# Microcontroller.net
KiCad netlist of a schematic drawn in Altium Designer
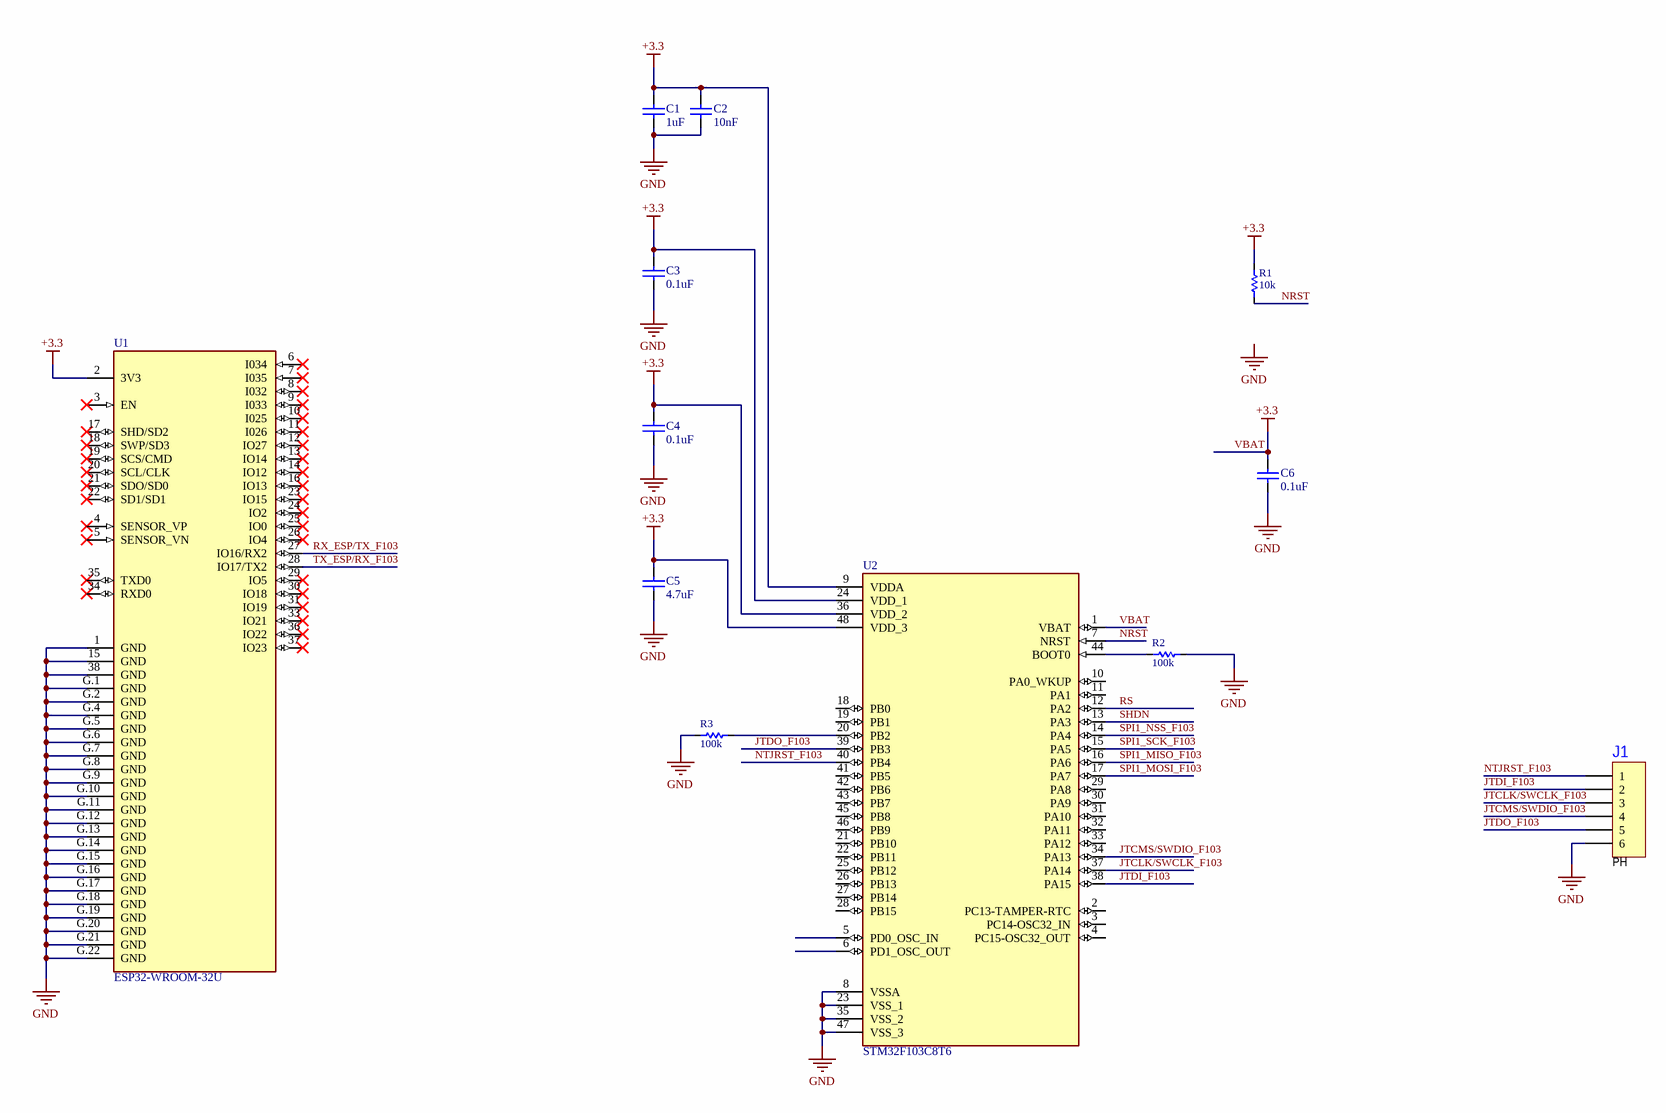
[diagram p0: Microcontroller.SchDoc]

(export (version "E")
  (design (tool "Eeschema 10.0.6"))
  (components
    (comp (ref "C1")
      (value "1uF")
      (footprint "CAPC2012X135N")
      (description "Capacitor SMD Ceramic Chip Cap 0.1uF 50V (0805) (AVX)")
      (fields (field (name "CREATED BY") "Zion Blue") (field (name "PUBLISHER") "Cynetik Group"))
      (libsource (lib "StylishSchematic") (part "CAP_0.1_50V_0805"))
    )
    (comp (ref "C2")
      (value "10nF")
      (footprint "CAPC2012X135N")
      (description "Capacitor SMD Ceramic Chip Cap 0.1uF 50V (0805) (AVX)")
      (fields (field (name "CREATED BY") "Zion Blue") (field (name "PUBLISHER") "Cynetik Group"))
      (libsource (lib "StylishSchematic") (part "CAP_0.1_50V_0805"))
    )
    (comp (ref "C3")
      (value "0.1uF")
      (footprint "CAPC2012X135N")
      (description "Capacitor SMD Ceramic Chip Cap 0.1uF 50V (0805) (AVX)")
      (fields (field (name "CREATED BY") "Zion Blue") (field (name "PUBLISHER") "Cynetik Group"))
      (libsource (lib "StylishSchematic") (part "CAP_0.1_50V_0805"))
    )
    (comp (ref "C4")
      (value "0.1uF")
      (footprint "CAPC2012X135N")
      (description "Capacitor SMD Ceramic Chip Cap 0.1uF 50V (0805) (AVX)")
      (fields (field (name "CREATED BY") "Zion Blue") (field (name "PUBLISHER") "Cynetik Group"))
      (libsource (lib "StylishSchematic") (part "CAP_0.1_50V_0805"))
    )
    (comp (ref "C5")
      (value "4.7uF")
      (footprint "CAPC2012X135N")
      (description "Capacitor SMD Ceramic Chip Cap 0.1uF 50V (0805) (AVX)")
      (fields (field (name "CREATED BY") "Zion Blue") (field (name "PUBLISHER") "Cynetik Group"))
      (libsource (lib "StylishSchematic") (part "CAP_0.1_50V_0805"))
    )
    (comp (ref "C6")
      (value "0.1uF")
      (footprint "CAPC2012X135N")
      (description "Capacitor SMD Ceramic Chip Cap 0.1uF 50V (0805) (AVX)")
      (fields (field (name "CREATED BY") "Zion Blue") (field (name "PUBLISHER") "Cynetik Group"))
      (libsource (lib "StylishSchematic") (part "CAP_0.1_50V_0805"))
    )
    (comp (ref "J1")
      (value "PH")
      (footprint "HDR1X6")
      (description "Connector 6 x 1 PIN Header 2.54 x 2.54 mm")
      (fields (field (name "PUBLISHER") "Altium Limited"))
      (libsource (lib "StylishSchematic") (part "Connector 6x1 Pin Header"))
    )
    (comp (ref "R1")
      (value "10k")
      (footprint "0805 MODIFICADO")
      (description "0805 100K OHM Resistor .")
      (libsource (lib "StylishSchematic") (part "RES_100K_1/8W_0805"))
    )
    (comp (ref "R2")
      (value "100k")
      (footprint "0805 MODIFICADO")
      (description "0805 100K OHM Resistor .")
      (libsource (lib "StylishSchematic") (part "RES_100K_1/8W_0805"))
    )
    (comp (ref "R3")
      (value "100k")
      (footprint "0805 MODIFICADO")
      (description "0805 100K OHM Resistor .")
      (libsource (lib "StylishSchematic") (part "RES_100K_1/8W_0805"))
    )
    (comp (ref "U1")
      (value "ESP32-WROOM-32U")
      (footprint "XCVR_ESP32-WROOM-32U")
      (fields (field (name "MF") "Espressif Systems"))
      (libsource (lib "StylishSchematic") (part "ESP32-WROOM-32U"))
    )
    (comp (ref "U2")
      (value "STM32F103C8T6")
      (footprint "QFP50P900X900X160-48N")
      (description "ARM® Cortex®-M3 STM32F1 Microcontroller IC 32-Bit 72MHz 64KB (64K x 8) FLASH 48-LQFP (7x7)")
      (fields (field (name "MF") "STMicroelectronics"))
      (libsource (lib "StylishSchematic") (part "STM32F103C8T6"))
    )
  )
  (nets
    (net (code "1") (name "+3.3") (class "Default")
      (node (ref "C1") (pin "2") (pinfunction "2_2") (pintype "passive"))
      (node (ref "C2") (pin "2") (pinfunction "2_2") (pintype "passive"))
      (node (ref "C3") (pin "2") (pinfunction "2_2") (pintype "passive"))
      (node (ref "C4") (pin "2") (pinfunction "2_2") (pintype "passive"))
      (node (ref "C5") (pin "2") (pinfunction "2_2") (pintype "passive"))
      (node (ref "C6") (pin "2") (pinfunction "2_2") (pintype "passive"))
      (node (ref "R1") (pin "2") (pinfunction "2_2") (pintype "passive"))
      (node (ref "U1") (pin "2") (pinfunction "3V3_2") (pintype "power_in"))
      (node (ref "U2") (pin "1") (pinfunction "VBAT_1") (pintype "bidirectional"))
      (node (ref "U2") (pin "24") (pinfunction "VDD_1_24") (pintype "power_in"))
      (node (ref "U2") (pin "36") (pinfunction "VDD_2_36") (pintype "power_in"))
      (node (ref "U2") (pin "48") (pinfunction "VDD_3_48") (pintype "power_in"))
      (node (ref "U2") (pin "9") (pinfunction "VDDA_9") (pintype "power_in"))
    )
    (net (code "2") (name "/JTCLK{slash}SWCLK_F103") (class "Default")
      (node (ref "J1") (pin "3") (pinfunction "3_3") (pintype "passive"))
      (node (ref "U2") (pin "37") (pinfunction "PA14_37") (pintype "bidirectional"))
    )
    (net (code "3") (name "/JTCMS{slash}SWDIO_F103") (class "Default")
      (node (ref "J1") (pin "4") (pinfunction "4_4") (pintype "passive"))
      (node (ref "U2") (pin "34") (pinfunction "PA13_34") (pintype "bidirectional"))
    )
    (net (code "4") (name "/JTDI_F103") (class "Default")
      (node (ref "J1") (pin "2") (pinfunction "2_2") (pintype "passive"))
      (node (ref "U2") (pin "38") (pinfunction "PA15_38") (pintype "bidirectional"))
    )
    (net (code "5") (name "/JTDO_F103") (class "Default")
      (node (ref "J1") (pin "5") (pinfunction "5_5") (pintype "passive"))
      (node (ref "U2") (pin "39") (pinfunction "PB3_39") (pintype "bidirectional"))
    )
    (net (code "6") (name "/NRST") (class "Default")
      (node (ref "R1") (pin "1") (pinfunction "1_1") (pintype "passive"))
      (node (ref "U2") (pin "7") (pinfunction "NRST_7") (pintype "input"))
    )
    (net (code "7") (name "/NTJRST_F103") (class "Default")
      (node (ref "J1") (pin "1") (pinfunction "1_1") (pintype "passive"))
      (node (ref "U2") (pin "40") (pinfunction "PB4_40") (pintype "bidirectional"))
    )
    (net (code "8") (name "/RS") (class "Default")
      (node (ref "U2") (pin "12") (pinfunction "PA2_12") (pintype "bidirectional"))
    )
    (net (code "9") (name "/RX_ESP{slash}TX_F103") (class "Default")
      (node (ref "U1") (pin "27") (pinfunction "IO16/RX2_27") (pintype "bidirectional"))
    )
    (net (code "10") (name "/SHDN") (class "Default")
      (node (ref "U2") (pin "13") (pinfunction "PA3_13") (pintype "bidirectional"))
    )
    (net (code "11") (name "/SPI1_MISO_F103") (class "Default")
      (node (ref "U2") (pin "16") (pinfunction "PA6_16") (pintype "bidirectional"))
    )
    (net (code "12") (name "/SPI1_MOSI_F103") (class "Default")
      (node (ref "U2") (pin "17") (pinfunction "PA7_17") (pintype "bidirectional"))
    )
    (net (code "13") (name "/SPI1_NSS_F103") (class "Default")
      (node (ref "U2") (pin "14") (pinfunction "PA4_14") (pintype "bidirectional"))
    )
    (net (code "14") (name "/SPI1_SCK_F103") (class "Default")
      (node (ref "U2") (pin "15") (pinfunction "PA5_15") (pintype "bidirectional"))
    )
    (net (code "15") (name "/TX_ESP{slash}RX_F103") (class "Default")
      (node (ref "U1") (pin "28") (pinfunction "IO17/TX2_28") (pintype "bidirectional"))
    )
    (net (code "16") (name "GND") (class "Default")
      (node (ref "C1") (pin "1") (pinfunction "1_1") (pintype "passive"))
      (node (ref "C2") (pin "1") (pinfunction "1_1") (pintype "passive"))
      (node (ref "C3") (pin "1") (pinfunction "1_1") (pintype "passive"))
      (node (ref "C4") (pin "1") (pinfunction "1_1") (pintype "passive"))
      (node (ref "C5") (pin "1") (pinfunction "1_1") (pintype "passive"))
      (node (ref "C6") (pin "1") (pinfunction "1_1") (pintype "passive"))
      (node (ref "J1") (pin "6") (pinfunction "6_6") (pintype "passive"))
      (node (ref "R2") (pin "2") (pinfunction "2_2") (pintype "passive"))
      (node (ref "R3") (pin "1") (pinfunction "1_1") (pintype "passive"))
      (node (ref "U1") (pin "1") (pinfunction "GND_1") (pintype "power_in"))
      (node (ref "U1") (pin "15") (pinfunction "GND_15") (pintype "power_in"))
      (node (ref "U1") (pin "38") (pinfunction "GND_38") (pintype "power_in"))
      (node (ref "U1") (pin "G.1") (pinfunction "GND_G.1") (pintype "power_in"))
      (node (ref "U1") (pin "G.10") (pinfunction "GND_G.10") (pintype "power_in"))
      (node (ref "U1") (pin "G.11") (pinfunction "GND_G.11") (pintype "power_in"))
      (node (ref "U1") (pin "G.12") (pinfunction "GND_G.12") (pintype "power_in"))
      (node (ref "U1") (pin "G.13") (pinfunction "GND_G.13") (pintype "power_in"))
      (node (ref "U1") (pin "G.14") (pinfunction "GND_G.14") (pintype "power_in"))
      (node (ref "U1") (pin "G.15") (pinfunction "GND_G.15") (pintype "power_in"))
      (node (ref "U1") (pin "G.16") (pinfunction "GND_G.16") (pintype "power_in"))
      (node (ref "U1") (pin "G.17") (pinfunction "GND_G.17") (pintype "power_in"))
      (node (ref "U1") (pin "G.18") (pinfunction "GND_G.18") (pintype "power_in"))
      (node (ref "U1") (pin "G.19") (pinfunction "GND_G.19") (pintype "power_in"))
      (node (ref "U1") (pin "G.2") (pinfunction "GND_G.2") (pintype "power_in"))
      (node (ref "U1") (pin "G.20") (pinfunction "GND_G.20") (pintype "power_in"))
      (node (ref "U1") (pin "G.21") (pinfunction "GND_G.21") (pintype "power_in"))
      (node (ref "U1") (pin "G.22") (pinfunction "GND_G.22") (pintype "power_in"))
      (node (ref "U1") (pin "G.4") (pinfunction "GND_G.4") (pintype "power_in"))
      (node (ref "U1") (pin "G.5") (pinfunction "GND_G.5") (pintype "power_in"))
      (node (ref "U1") (pin "G.6") (pinfunction "GND_G.6") (pintype "power_in"))
      (node (ref "U1") (pin "G.7") (pinfunction "GND_G.7") (pintype "power_in"))
      (node (ref "U1") (pin "G.8") (pinfunction "GND_G.8") (pintype "power_in"))
      (node (ref "U1") (pin "G.9") (pinfunction "GND_G.9") (pintype "power_in"))
      (node (ref "U2") (pin "23") (pinfunction "VSS_1_23") (pintype "power_in"))
      (node (ref "U2") (pin "35") (pinfunction "VSS_2_35") (pintype "power_in"))
      (node (ref "U2") (pin "47") (pinfunction "VSS_3_47") (pintype "power_in"))
      (node (ref "U2") (pin "8") (pinfunction "VSSA_8") (pintype "power_in"))
    )
    (net (code "17") (name "Net-(U2-BOOT0)") (class "Default")
      (node (ref "R2") (pin "1") (pinfunction "1_1") (pintype "passive"))
      (node (ref "U2") (pin "44") (pinfunction "BOOT0_44") (pintype "input"))
    )
    (net (code "18") (name "Net-(U2-PB2)") (class "Default")
      (node (ref "R3") (pin "2") (pinfunction "2_2") (pintype "passive"))
      (node (ref "U2") (pin "20") (pinfunction "PB2_20") (pintype "bidirectional"))
    )
    (net (code "19") (name "unconnected-(U1-EN-Pad3)") (class "Default")
      (node (ref "U1") (pin "3") (pinfunction "EN_3") (pintype "input+no_connect"))
    )
    (net (code "20") (name "unconnected-(U1-I025-Pad10)") (class "Default")
      (node (ref "U1") (pin "10") (pinfunction "I025_10") (pintype "bidirectional+no_connect"))
    )
    (net (code "21") (name "unconnected-(U1-I026-Pad11)") (class "Default")
      (node (ref "U1") (pin "11") (pinfunction "I026_11") (pintype "bidirectional+no_connect"))
    )
    (net (code "22") (name "unconnected-(U1-I032-Pad8)") (class "Default")
      (node (ref "U1") (pin "8") (pinfunction "I032_8") (pintype "bidirectional+no_connect"))
    )
    (net (code "23") (name "unconnected-(U1-I033-Pad9)") (class "Default")
      (node (ref "U1") (pin "9") (pinfunction "I033_9") (pintype "bidirectional+no_connect"))
    )
    (net (code "24") (name "unconnected-(U1-I034-Pad6)") (class "Default")
      (node (ref "U1") (pin "6") (pinfunction "I034_6") (pintype "input+no_connect"))
    )
    (net (code "25") (name "unconnected-(U1-I035-Pad7)") (class "Default")
      (node (ref "U1") (pin "7") (pinfunction "I035_7") (pintype "input+no_connect"))
    )
    (net (code "26") (name "unconnected-(U1-IO0-Pad25)") (class "Default")
      (node (ref "U1") (pin "25") (pinfunction "IO0_25") (pintype "bidirectional+no_connect"))
    )
    (net (code "27") (name "unconnected-(U1-IO2-Pad24)") (class "Default")
      (node (ref "U1") (pin "24") (pinfunction "IO2_24") (pintype "bidirectional+no_connect"))
    )
    (net (code "28") (name "unconnected-(U1-IO4-Pad26)") (class "Default")
      (node (ref "U1") (pin "26") (pinfunction "IO4_26") (pintype "bidirectional+no_connect"))
    )
    (net (code "29") (name "unconnected-(U1-IO5-Pad29)") (class "Default")
      (node (ref "U1") (pin "29") (pinfunction "IO5_29") (pintype "bidirectional+no_connect"))
    )
    (net (code "30") (name "unconnected-(U1-IO12-Pad14)") (class "Default")
      (node (ref "U1") (pin "14") (pinfunction "IO12_14") (pintype "bidirectional+no_connect"))
    )
    (net (code "31") (name "unconnected-(U1-IO13-Pad16)") (class "Default")
      (node (ref "U1") (pin "16") (pinfunction "IO13_16") (pintype "bidirectional+no_connect"))
    )
    (net (code "32") (name "unconnected-(U1-IO14-Pad13)") (class "Default")
      (node (ref "U1") (pin "13") (pinfunction "IO14_13") (pintype "bidirectional+no_connect"))
    )
    (net (code "33") (name "unconnected-(U1-IO15-Pad23)") (class "Default")
      (node (ref "U1") (pin "23") (pinfunction "IO15_23") (pintype "bidirectional+no_connect"))
    )
    (net (code "34") (name "unconnected-(U1-IO18-Pad30)") (class "Default")
      (node (ref "U1") (pin "30") (pinfunction "IO18_30") (pintype "bidirectional+no_connect"))
    )
    (net (code "35") (name "unconnected-(U1-IO19-Pad31)") (class "Default")
      (node (ref "U1") (pin "31") (pinfunction "IO19_31") (pintype "bidirectional+no_connect"))
    )
    (net (code "36") (name "unconnected-(U1-IO21-Pad33)") (class "Default")
      (node (ref "U1") (pin "33") (pinfunction "IO21_33") (pintype "bidirectional+no_connect"))
    )
    (net (code "37") (name "unconnected-(U1-IO22-Pad36)") (class "Default")
      (node (ref "U1") (pin "36") (pinfunction "IO22_36") (pintype "bidirectional+no_connect"))
    )
    (net (code "38") (name "unconnected-(U1-IO23-Pad37)") (class "Default")
      (node (ref "U1") (pin "37") (pinfunction "IO23_37") (pintype "bidirectional+no_connect"))
    )
    (net (code "39") (name "unconnected-(U1-IO27-Pad12)") (class "Default")
      (node (ref "U1") (pin "12") (pinfunction "IO27_12") (pintype "bidirectional+no_connect"))
    )
    (net (code "40") (name "unconnected-(U1-RXD0-Pad34)") (class "Default")
      (node (ref "U1") (pin "34") (pinfunction "RXD0_34") (pintype "bidirectional+no_connect"))
    )
    (net (code "41") (name "unconnected-(U1-SCL{slash}CLK-Pad20)") (class "Default")
      (node (ref "U1") (pin "20") (pinfunction "SCL/CLK_20") (pintype "bidirectional+no_connect"))
    )
    (net (code "42") (name "unconnected-(U1-SCS{slash}CMD-Pad19)") (class "Default")
      (node (ref "U1") (pin "19") (pinfunction "SCS/CMD_19") (pintype "bidirectional+no_connect"))
    )
    (net (code "43") (name "unconnected-(U1-SD1{slash}SD1-Pad22)") (class "Default")
      (node (ref "U1") (pin "22") (pinfunction "SD1/SD1_22") (pintype "bidirectional+no_connect"))
    )
    (net (code "44") (name "unconnected-(U1-SDO{slash}SD0-Pad21)") (class "Default")
      (node (ref "U1") (pin "21") (pinfunction "SDO/SD0_21") (pintype "bidirectional+no_connect"))
    )
    (net (code "45") (name "unconnected-(U1-SENSOR_VN-Pad5)") (class "Default")
      (node (ref "U1") (pin "5") (pinfunction "SENSOR_VN_5") (pintype "input+no_connect"))
    )
    (net (code "46") (name "unconnected-(U1-SENSOR_VP-Pad4)") (class "Default")
      (node (ref "U1") (pin "4") (pinfunction "SENSOR_VP_4") (pintype "input+no_connect"))
    )
    (net (code "47") (name "unconnected-(U1-SHD{slash}SD2-Pad17)") (class "Default")
      (node (ref "U1") (pin "17") (pinfunction "SHD/SD2_17") (pintype "bidirectional+no_connect"))
    )
    (net (code "48") (name "unconnected-(U1-SWP{slash}SD3-Pad18)") (class "Default")
      (node (ref "U1") (pin "18") (pinfunction "SWP/SD3_18") (pintype "bidirectional+no_connect"))
    )
    (net (code "49") (name "unconnected-(U1-TXD0-Pad35)") (class "Default")
      (node (ref "U1") (pin "35") (pinfunction "TXD0_35") (pintype "bidirectional+no_connect"))
    )
    (net (code "50") (name "unconnected-(U2-PA0_WKUP-Pad10)") (class "Default")
      (node (ref "U2") (pin "10") (pinfunction "PA0_WKUP_10") (pintype "bidirectional"))
    )
    (net (code "51") (name "unconnected-(U2-PA1-Pad11)") (class "Default")
      (node (ref "U2") (pin "11") (pinfunction "PA1_11") (pintype "bidirectional"))
    )
    (net (code "52") (name "unconnected-(U2-PA8-Pad29)") (class "Default")
      (node (ref "U2") (pin "29") (pinfunction "PA8_29") (pintype "bidirectional"))
    )
    (net (code "53") (name "unconnected-(U2-PA9-Pad30)") (class "Default")
      (node (ref "U2") (pin "30") (pinfunction "PA9_30") (pintype "bidirectional"))
    )
    (net (code "54") (name "unconnected-(U2-PA10-Pad31)") (class "Default")
      (node (ref "U2") (pin "31") (pinfunction "PA10_31") (pintype "bidirectional"))
    )
    (net (code "55") (name "unconnected-(U2-PA11-Pad32)") (class "Default")
      (node (ref "U2") (pin "32") (pinfunction "PA11_32") (pintype "bidirectional"))
    )
    (net (code "56") (name "unconnected-(U2-PA12-Pad33)") (class "Default")
      (node (ref "U2") (pin "33") (pinfunction "PA12_33") (pintype "bidirectional"))
    )
    (net (code "57") (name "unconnected-(U2-PB0-Pad18)") (class "Default")
      (node (ref "U2") (pin "18") (pinfunction "PB0_18") (pintype "bidirectional"))
    )
    (net (code "58") (name "unconnected-(U2-PB1-Pad19)") (class "Default")
      (node (ref "U2") (pin "19") (pinfunction "PB1_19") (pintype "bidirectional"))
    )
    (net (code "59") (name "unconnected-(U2-PB5-Pad41)") (class "Default")
      (node (ref "U2") (pin "41") (pinfunction "PB5_41") (pintype "bidirectional"))
    )
    (net (code "60") (name "unconnected-(U2-PB6-Pad42)") (class "Default")
      (node (ref "U2") (pin "42") (pinfunction "PB6_42") (pintype "bidirectional"))
    )
    (net (code "61") (name "unconnected-(U2-PB7-Pad43)") (class "Default")
      (node (ref "U2") (pin "43") (pinfunction "PB7_43") (pintype "bidirectional"))
    )
    (net (code "62") (name "unconnected-(U2-PB8-Pad45)") (class "Default")
      (node (ref "U2") (pin "45") (pinfunction "PB8_45") (pintype "bidirectional"))
    )
    (net (code "63") (name "unconnected-(U2-PB9-Pad46)") (class "Default")
      (node (ref "U2") (pin "46") (pinfunction "PB9_46") (pintype "bidirectional"))
    )
    (net (code "64") (name "unconnected-(U2-PB10-Pad21)") (class "Default")
      (node (ref "U2") (pin "21") (pinfunction "PB10_21") (pintype "bidirectional"))
    )
    (net (code "65") (name "unconnected-(U2-PB11-Pad22)") (class "Default")
      (node (ref "U2") (pin "22") (pinfunction "PB11_22") (pintype "bidirectional"))
    )
    (net (code "66") (name "unconnected-(U2-PB12-Pad25)") (class "Default")
      (node (ref "U2") (pin "25") (pinfunction "PB12_25") (pintype "bidirectional"))
    )
    (net (code "67") (name "unconnected-(U2-PB13-Pad26)") (class "Default")
      (node (ref "U2") (pin "26") (pinfunction "PB13_26") (pintype "bidirectional"))
    )
    (net (code "68") (name "unconnected-(U2-PB14-Pad27)") (class "Default")
      (node (ref "U2") (pin "27") (pinfunction "PB14_27") (pintype "bidirectional"))
    )
    (net (code "69") (name "unconnected-(U2-PB15-Pad28)") (class "Default")
      (node (ref "U2") (pin "28") (pinfunction "PB15_28") (pintype "bidirectional"))
    )
    (net (code "70") (name "unconnected-(U2-PC13-TAMPER-RTC-Pad2)") (class "Default")
      (node (ref "U2") (pin "2") (pinfunction "PC13-TAMPER-RTC_2") (pintype "bidirectional"))
    )
    (net (code "71") (name "unconnected-(U2-PC14-OSC32_IN-Pad3)") (class "Default")
      (node (ref "U2") (pin "3") (pinfunction "PC14-OSC32_IN_3") (pintype "bidirectional"))
    )
    (net (code "72") (name "unconnected-(U2-PC15-OSC32_OUT-Pad4)") (class "Default")
      (node (ref "U2") (pin "4") (pinfunction "PC15-OSC32_OUT_4") (pintype "bidirectional"))
    )
    (net (code "73") (name "unconnected-(U2-PD0_OSC_IN-Pad5)") (class "Default")
      (node (ref "U2") (pin "5") (pinfunction "PD0_OSC_IN_5") (pintype "bidirectional"))
    )
    (net (code "74") (name "unconnected-(U2-PD1_OSC_OUT-Pad6)") (class "Default")
      (node (ref "U2") (pin "6") (pinfunction "PD1_OSC_OUT_6") (pintype "bidirectional"))
    )
  )
)
